# motorEncoder.net
KiCad netlist of a schematic drawn in Altium Designer
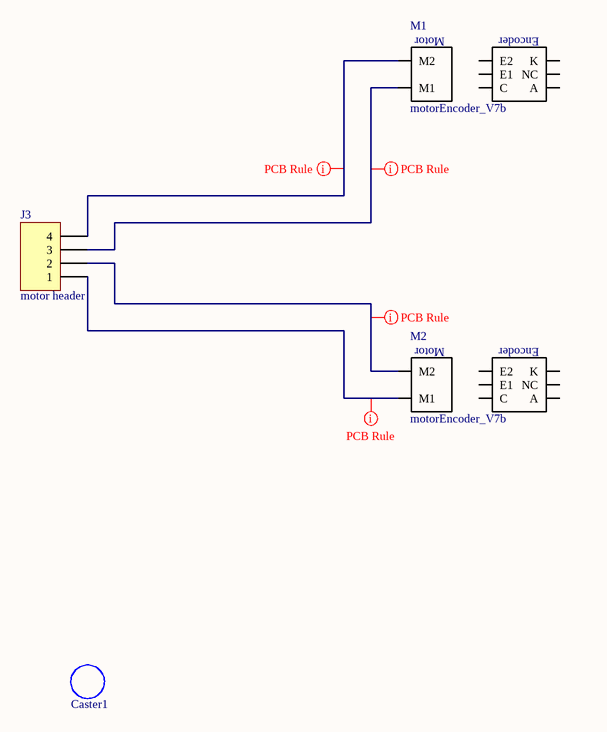
[diagram p0: motorEncoder.SchDoc]

(export (version "E")
  (design (tool "Eeschema 10.0.6"))
  (components
    (comp (ref "Caster1")
      (value "non connect")
      (footprint "3/4\"CASTER2")
      (description "This is just a space saver to get the caster onto the pcb")
      (libsource (lib "mrone") (part "Caster 3/4in"))
    )
    (comp (ref "J3")
      (value "motor header")
      (footprint "HDR1X4")
      (description "Header, 4-Pin")
      (fields (field (name "PUBLISHER") "Altium Limited"))
      (libsource (lib "Miscellaneous Connectors") (part "Header 4"))
    )
    (comp (ref "M1")
      (value "motorEncoder_V7b")
      (footprint "motorEncoder_V7b")
      (libsource (lib "mrone") (part "motorEncoder_V7b"))
    )
    (comp (ref "M2")
      (value "motorEncoder_V7b")
      (footprint "motorEncoder_V7b")
      (libsource (lib "mrone") (part "motorEncoder_V7b"))
    )
  )
  (nets
    (net (code "1") (name "Net-(J3-Pad1)") (class "Default")
      (node (ref "J3") (pin "1") (pinfunction "1_1") (pintype "passive"))
      (node (ref "M2") (pin "M1") (pinfunction "M1_M1") (pintype "passive"))
    )
    (net (code "2") (name "Net-(J3-Pad2)") (class "Default")
      (node (ref "J3") (pin "2") (pinfunction "2_2") (pintype "passive"))
      (node (ref "M2") (pin "M2") (pinfunction "M2_M2") (pintype "passive"))
    )
    (net (code "3") (name "Net-(J3-Pad3)") (class "Default")
      (node (ref "J3") (pin "3") (pinfunction "3_3") (pintype "passive"))
      (node (ref "M1") (pin "M1") (pinfunction "M1_M1") (pintype "passive"))
    )
    (net (code "4") (name "Net-(J3-Pad4)") (class "Default")
      (node (ref "J3") (pin "4") (pinfunction "4_4") (pintype "passive"))
      (node (ref "M1") (pin "M2") (pinfunction "M2_M2") (pintype "passive"))
    )
    (net (code "5") (name "unconnected-(M1-PadA)") (class "Default")
      (node (ref "M1") (pin "A") (pinfunction "A_A") (pintype "passive"))
    )
    (net (code "6") (name "unconnected-(M1-PadC)") (class "Default")
      (node (ref "M1") (pin "C") (pinfunction "C_C") (pintype "passive"))
    )
    (net (code "7") (name "unconnected-(M1-PadE1)") (class "Default")
      (node (ref "M1") (pin "E1") (pinfunction "E1_E1") (pintype "passive"))
    )
    (net (code "8") (name "unconnected-(M1-PadE2)") (class "Default")
      (node (ref "M1") (pin "E2") (pinfunction "E2_E2") (pintype "passive"))
    )
    (net (code "9") (name "unconnected-(M1-PadK)") (class "Default")
      (node (ref "M1") (pin "K") (pinfunction "K_K") (pintype "passive"))
    )
    (net (code "10") (name "unconnected-(M1-PadNC)") (class "Default")
      (node (ref "M1") (pin "NC") (pinfunction "NC_NC") (pintype "passive"))
    )
    (net (code "11") (name "unconnected-(M2-PadA)") (class "Default")
      (node (ref "M2") (pin "A") (pinfunction "A_A") (pintype "passive"))
    )
    (net (code "12") (name "unconnected-(M2-PadC)") (class "Default")
      (node (ref "M2") (pin "C") (pinfunction "C_C") (pintype "passive"))
    )
    (net (code "13") (name "unconnected-(M2-PadE1)") (class "Default")
      (node (ref "M2") (pin "E1") (pinfunction "E1_E1") (pintype "passive"))
    )
    (net (code "14") (name "unconnected-(M2-PadE2)") (class "Default")
      (node (ref "M2") (pin "E2") (pinfunction "E2_E2") (pintype "passive"))
    )
    (net (code "15") (name "unconnected-(M2-PadK)") (class "Default")
      (node (ref "M2") (pin "K") (pinfunction "K_K") (pintype "passive"))
    )
    (net (code "16") (name "unconnected-(M2-PadNC)") (class "Default")
      (node (ref "M2") (pin "NC") (pinfunction "NC_NC") (pintype "passive"))
    )
  )
)
